# ADC.net
KiCad netlist of a schematic drawn in Altium Designer
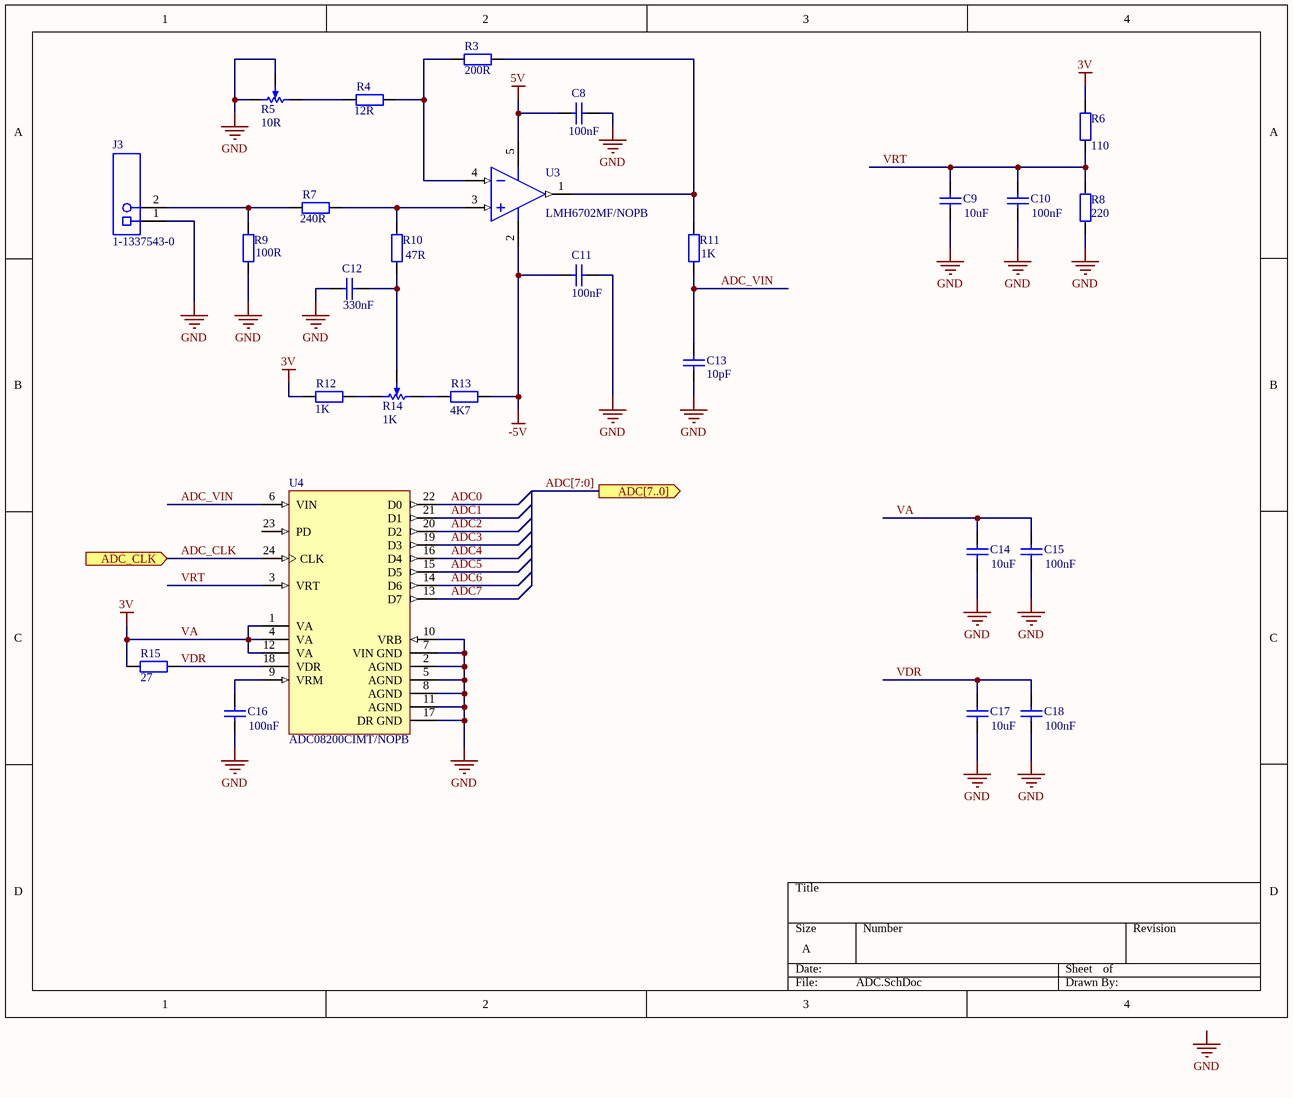
[diagram p0: ADC.SchDoc]

(export (version "E")
  (design (tool "Eeschema 10.0.6"))
  (components
    (comp (ref "C8")
      (value "100nF")
      (footprint "RAD-0.3")
      (description "Capacitor")
      (fields (field (name "Comment") "Cap") (field (name "PUBLISHER") "Altium Limited"))
      (libsource (lib "Miscellaneous Devices") (part "Cap"))
    )
    (comp (ref "C9")
      (value "10uF")
      (footprint "RAD-0.3")
      (description "Capacitor")
      (fields (field (name "Comment") "Cap") (field (name "PUBLISHER") "Altium Limited"))
      (libsource (lib "Miscellaneous Devices") (part "Cap"))
    )
    (comp (ref "C10")
      (value "100nF")
      (footprint "RAD-0.3")
      (description "Capacitor")
      (fields (field (name "Comment") "Cap") (field (name "PUBLISHER") "Altium Limited"))
      (libsource (lib "Miscellaneous Devices") (part "Cap"))
    )
    (comp (ref "C11")
      (value "100nF")
      (footprint "RAD-0.3")
      (description "Capacitor")
      (fields (field (name "Comment") "Cap") (field (name "PUBLISHER") "Altium Limited"))
      (libsource (lib "Miscellaneous Devices") (part "Cap"))
    )
    (comp (ref "C12")
      (value "330nF")
      (footprint "RAD-0.3")
      (description "Capacitor")
      (fields (field (name "Comment") "Cap") (field (name "PUBLISHER") "Altium Limited"))
      (libsource (lib "Miscellaneous Devices") (part "Cap"))
    )
    (comp (ref "C13")
      (value "10pF")
      (footprint "RAD-0.3")
      (description "Capacitor")
      (fields (field (name "Comment") "Cap") (field (name "PUBLISHER") "Altium Limited"))
      (libsource (lib "Miscellaneous Devices") (part "Cap"))
    )
    (comp (ref "C14")
      (value "10uF")
      (footprint "RAD-0.3")
      (description "Capacitor")
      (fields (field (name "Comment") "Cap") (field (name "PUBLISHER") "Altium Limited"))
      (libsource (lib "Miscellaneous Devices") (part "Cap"))
    )
    (comp (ref "C15")
      (value "100nF")
      (footprint "RAD-0.3")
      (description "Capacitor")
      (fields (field (name "Comment") "Cap") (field (name "PUBLISHER") "Altium Limited"))
      (libsource (lib "Miscellaneous Devices") (part "Cap"))
    )
    (comp (ref "C16")
      (value "100nF")
      (footprint "RAD-0.3")
      (description "Capacitor")
      (fields (field (name "Comment") "Cap") (field (name "PUBLISHER") "Altium Limited"))
      (libsource (lib "Miscellaneous Devices") (part "Cap"))
    )
    (comp (ref "C17")
      (value "10uF")
      (footprint "RAD-0.3")
      (description "Capacitor")
      (fields (field (name "Comment") "Cap") (field (name "PUBLISHER") "Altium Limited"))
      (libsource (lib "Miscellaneous Devices") (part "Cap"))
    )
    (comp (ref "C18")
      (value "100nF")
      (footprint "RAD-0.3")
      (description "Capacitor")
      (fields (field (name "Comment") "Cap") (field (name "PUBLISHER") "Altium Limited"))
      (libsource (lib "Miscellaneous Devices") (part "Cap"))
    )
    (comp (ref "J3")
      (value "1-1337543-0")
      (footprint "TECO-1-1337543-0_V")
      (fields (field (name "MANUFACTURER") "TE Connectivity"))
      (libsource (lib "Altium Content Vault") (part "CN-1P-F-R2_A"))
    )
    (comp (ref "R3")
      (value "200R")
      (footprint "AXIAL-0.4")
      (description "Resistor")
      (fields (field (name "Comment") "Res2") (field (name "PUBLISHER") "Altium Limited"))
      (libsource (lib "") (part "Res2_2"))
    )
    (comp (ref "R4")
      (value "12R")
      (footprint "AXIAL-0.4")
      (description "Resistor")
      (fields (field (name "Comment") "Res2") (field (name "PUBLISHER") "Altium Limited"))
      (libsource (lib "") (part "Res2_2"))
    )
    (comp (ref "R5")
      (value "10R")
      (footprint "POT4MM-2")
      (description "Square Trimming Potentiometer")
      (fields (field (name "PUBLISHER") "Altium Limited"))
      (libsource (lib "Miscellaneous Devices") (part "RPot SM"))
    )
    (comp (ref "R6")
      (value "110")
      (footprint "AXIAL-0.4")
      (description "Resistor")
      (fields (field (name "Comment") "Res2") (field (name "PUBLISHER") "Altium Limited"))
      (libsource (lib "Miscellaneous Devices") (part "Res2"))
    )
    (comp (ref "R7")
      (value "240R")
      (footprint "AXIAL-0.4")
      (description "Resistor")
      (fields (field (name "Comment") "Res2") (field (name "PUBLISHER") "Altium Limited"))
      (libsource (lib "") (part "Res2_2"))
    )
    (comp (ref "R8")
      (value "220")
      (footprint "AXIAL-0.4")
      (description "Resistor")
      (fields (field (name "Comment") "Res2") (field (name "PUBLISHER") "Altium Limited"))
      (libsource (lib "Miscellaneous Devices") (part "Res2"))
    )
    (comp (ref "R9")
      (value "100R")
      (footprint "AXIAL-0.4")
      (description "Resistor")
      (fields (field (name "Comment") "Res2") (field (name "PUBLISHER") "Altium Limited"))
      (libsource (lib "Miscellaneous Devices") (part "Res2"))
    )
    (comp (ref "R10")
      (value "47R")
      (footprint "AXIAL-0.4")
      (description "Resistor")
      (fields (field (name "Comment") "Res2") (field (name "PUBLISHER") "Altium Limited"))
      (libsource (lib "Miscellaneous Devices") (part "Res2"))
    )
    (comp (ref "R11")
      (value "1K")
      (footprint "AXIAL-0.4")
      (description "Resistor")
      (fields (field (name "Comment") "Res2") (field (name "PUBLISHER") "Altium Limited"))
      (libsource (lib "Miscellaneous Devices") (part "Res2"))
    )
    (comp (ref "R12")
      (value "1K")
      (footprint "AXIAL-0.4")
      (description "Resistor")
      (fields (field (name "Comment") "Res2") (field (name "PUBLISHER") "Altium Limited"))
      (libsource (lib "") (part "Res2_1"))
    )
    (comp (ref "R13")
      (value "4K7")
      (footprint "AXIAL-0.4")
      (description "Resistor")
      (fields (field (name "Comment") "Res2") (field (name "PUBLISHER") "Altium Limited"))
      (libsource (lib "") (part "Res2_1"))
    )
    (comp (ref "R14")
      (value "1K")
      (footprint "POT4MM-2")
      (description "Square Trimming Potentiometer")
      (fields (field (name "PUBLISHER") "Altium Limited"))
      (libsource (lib "Miscellaneous Devices") (part "RPot SM"))
    )
    (comp (ref "R15")
      (value "27")
      (footprint "AXIAL-0.4")
      (description "Resistor")
      (fields (field (name "Comment") "Res2") (field (name "PUBLISHER") "Altium Limited"))
      (libsource (lib "") (part "Res2_1"))
    )
    (comp (ref "U3")
      (value "LMH6702MF/NOPB")
      (footprint "DBV0005A_N")
      (description "1.7 GHz, Ultra Low Distortion, Wideband Op Amp, 5-pin SOT-23, Pb-Free")
      (fields (field (name "MANUFACTURER") "Texas Instruments"))
      (libsource (lib "Altium Content Vault") (part "AMP-OPA-LM7121-5"))
    )
    (comp (ref "U4")
      (value "ADC08200CIMT/NOPB")
      (footprint "PW0024A_M")
      (fields (field (name "MANUFACTURER") "Texas Instruments"))
      (libsource (lib "Altium Content Vault") (part "CON-ADC-ADC08L060CIMT"))
    )
  )
  (nets
    (net (code "2") (name "-5V") (class "Default")
      (node (ref "C11") (pin "1") (pinfunction "1_1") (pintype "passive"))
      (node (ref "R13") (pin "1") (pinfunction "1_1") (pintype "passive"))
      (node (ref "U3") (pin "2") (pinfunction "V-_2") (pintype "power_in"))
    )
    (net (code "3") (name "/ADC0") (class "Default")
      (node (ref "U4") (pin "22") (pinfunction "D0_22") (pintype "output"))
    )
    (net (code "4") (name "/ADC1") (class "Default")
      (node (ref "U4") (pin "21") (pinfunction "D1_21") (pintype "output"))
    )
    (net (code "5") (name "/ADC2") (class "Default")
      (node (ref "U4") (pin "20") (pinfunction "D2_20") (pintype "output"))
    )
    (net (code "6") (name "/ADC3") (class "Default")
      (node (ref "U4") (pin "19") (pinfunction "D3_19") (pintype "output"))
    )
    (net (code "7") (name "/ADC4") (class "Default")
      (node (ref "U4") (pin "16") (pinfunction "D4_16") (pintype "output"))
    )
    (net (code "8") (name "/ADC5") (class "Default")
      (node (ref "U4") (pin "15") (pinfunction "D5_15") (pintype "output"))
    )
    (net (code "9") (name "/ADC6") (class "Default")
      (node (ref "U4") (pin "14") (pinfunction "D6_14") (pintype "output"))
    )
    (net (code "10") (name "/ADC7") (class "Default")
      (node (ref "U4") (pin "13") (pinfunction "D7_13") (pintype "output"))
    )
    (net (code "11") (name "/ADC_CLK") (class "Default")
      (node (ref "U4") (pin "24") (pinfunction "CLK_24") (pintype "input"))
    )
    (net (code "12") (name "/ADC_VIN") (class "Default")
      (node (ref "C13") (pin "2") (pinfunction "2_2") (pintype "passive"))
      (node (ref "R11") (pin "1") (pinfunction "1_1") (pintype "passive"))
      (node (ref "U4") (pin "6") (pinfunction "VIN_6") (pintype "input"))
    )
    (net (code "13") (name "/VDR") (class "Default")
      (node (ref "C17") (pin "2") (pinfunction "2_2") (pintype "passive"))
      (node (ref "C18") (pin "2") (pinfunction "2_2") (pintype "passive"))
      (node (ref "R15") (pin "1") (pinfunction "1_1") (pintype "passive"))
      (node (ref "U4") (pin "18") (pinfunction "VDR_18") (pintype "power_in"))
    )
    (net (code "14") (name "/VRT") (class "Default")
      (node (ref "C10") (pin "2") (pinfunction "2_2") (pintype "passive"))
      (node (ref "C9") (pin "2") (pinfunction "2_2") (pintype "passive"))
      (node (ref "R6") (pin "1") (pinfunction "1_1") (pintype "passive"))
      (node (ref "R8") (pin "2") (pinfunction "2_2") (pintype "passive"))
      (node (ref "U4") (pin "3") (pinfunction "VRT_3") (pintype "input"))
    )
    (net (code "16") (name "3V") (class "Default")
      (node (ref "C14") (pin "2") (pinfunction "2_2") (pintype "passive"))
      (node (ref "C15") (pin "2") (pinfunction "2_2") (pintype "passive"))
      (node (ref "R12") (pin "2") (pinfunction "2_2") (pintype "passive"))
      (node (ref "R15") (pin "2") (pinfunction "2_2") (pintype "passive"))
      (node (ref "R6") (pin "2") (pinfunction "2_2") (pintype "passive"))
      (node (ref "U4") (pin "1") (pinfunction "VA_1") (pintype "power_in"))
      (node (ref "U4") (pin "12") (pinfunction "VA_12") (pintype "power_in"))
      (node (ref "U4") (pin "4") (pinfunction "VA_4") (pintype "power_in"))
    )
    (net (code "17") (name "5V") (class "Default")
      (node (ref "C8") (pin "1") (pinfunction "1_1") (pintype "passive"))
      (node (ref "U3") (pin "5") (pinfunction "V+_5") (pintype "power_in"))
    )
    (net (code "18") (name "GND") (class "Default")
      (node (ref "C10") (pin "1") (pinfunction "1_1") (pintype "passive"))
      (node (ref "C11") (pin "2") (pinfunction "2_2") (pintype "passive"))
      (node (ref "C12") (pin "1") (pinfunction "1_1") (pintype "passive"))
      (node (ref "C13") (pin "1") (pinfunction "1_1") (pintype "passive"))
      (node (ref "C14") (pin "1") (pinfunction "1_1") (pintype "passive"))
      (node (ref "C15") (pin "1") (pinfunction "1_1") (pintype "passive"))
      (node (ref "C16") (pin "1") (pinfunction "1_1") (pintype "passive"))
      (node (ref "C17") (pin "1") (pinfunction "1_1") (pintype "passive"))
      (node (ref "C18") (pin "1") (pinfunction "1_1") (pintype "passive"))
      (node (ref "C8") (pin "2") (pinfunction "2_2") (pintype "passive"))
      (node (ref "C9") (pin "1") (pinfunction "1_1") (pintype "passive"))
      (node (ref "J3") (pin "1") (pinfunction "1_1") (pintype "passive"))
      (node (ref "R5") (pin "CW") (pinfunction "+_CW") (pintype "passive"))
      (node (ref "R5") (pin "W") (pinfunction "W_W") (pintype "passive"))
      (node (ref "R8") (pin "1") (pinfunction "1_1") (pintype "passive"))
      (node (ref "R9") (pin "1") (pinfunction "1_1") (pintype "passive"))
      (node (ref "U4") (pin "10") (pinfunction "VRB_10") (pintype "input"))
      (node (ref "U4") (pin "11") (pinfunction "AGND_11") (pintype "power_in"))
      (node (ref "U4") (pin "17") (pinfunction "DR_GND_17") (pintype "power_in"))
      (node (ref "U4") (pin "2") (pinfunction "AGND_2") (pintype "power_in"))
      (node (ref "U4") (pin "5") (pinfunction "AGND_5") (pintype "power_in"))
      (node (ref "U4") (pin "7") (pinfunction "VIN_GND_7") (pintype "power_in"))
      (node (ref "U4") (pin "8") (pinfunction "AGND_8") (pintype "power_in"))
    )
    (net (code "19") (name "Net-(C12-Pad2)") (class "Default")
      (node (ref "C12") (pin "2") (pinfunction "2_2") (pintype "passive"))
      (node (ref "R10") (pin "1") (pinfunction "1_1") (pintype "passive"))
      (node (ref "R14") (pin "W") (pinfunction "W_W") (pintype "passive"))
    )
    (net (code "20") (name "Net-(J3-Pad2)") (class "Default")
      (node (ref "J3") (pin "2") (pinfunction "2_2") (pintype "passive"))
      (node (ref "R7") (pin "1") (pinfunction "1_1") (pintype "passive"))
      (node (ref "R9") (pin "2") (pinfunction "2_2") (pintype "passive"))
    )
    (net (code "21") (name "Net-(R5--)") (class "Default")
      (node (ref "R4") (pin "1") (pinfunction "1_1") (pintype "passive"))
      (node (ref "R5") (pin "CCW") (pinfunction "-_CCW") (pintype "passive"))
    )
    (net (code "22") (name "Net-(R14-+)") (class "Default")
      (node (ref "R12") (pin "1") (pinfunction "1_1") (pintype "passive"))
      (node (ref "R14") (pin "CW") (pinfunction "+_CW") (pintype "passive"))
    )
    (net (code "23") (name "Net-(R14--)") (class "Default")
      (node (ref "R13") (pin "2") (pinfunction "2_2") (pintype "passive"))
      (node (ref "R14") (pin "CCW") (pinfunction "-_CCW") (pintype "passive"))
    )
    (net (code "24") (name "Net-(U3-IN+)") (class "Default")
      (node (ref "R10") (pin "2") (pinfunction "2_2") (pintype "passive"))
      (node (ref "R7") (pin "2") (pinfunction "2_2") (pintype "passive"))
      (node (ref "U3") (pin "3") (pinfunction "IN+_3") (pintype "input"))
    )
    (net (code "25") (name "Net-(U3-IN-)") (class "Default")
      (node (ref "R3") (pin "1") (pinfunction "1_1") (pintype "passive"))
      (node (ref "R4") (pin "2") (pinfunction "2_2") (pintype "passive"))
      (node (ref "U3") (pin "4") (pinfunction "IN-_4") (pintype "input"))
    )
    (net (code "26") (name "Net-(U3-OUT)") (class "Default")
      (node (ref "R11") (pin "2") (pinfunction "2_2") (pintype "passive"))
      (node (ref "R3") (pin "2") (pinfunction "2_2") (pintype "passive"))
      (node (ref "U3") (pin "1") (pinfunction "OUT_1") (pintype "output"))
    )
    (net (code "27") (name "Net-(U4-VRM)") (class "Default")
      (node (ref "C16") (pin "2") (pinfunction "2_2") (pintype "passive"))
      (node (ref "U4") (pin "9") (pinfunction "VRM_9") (pintype "input"))
    )
    (net (code "28") (name "unconnected-(U4-PD-Pad23)") (class "Default")
      (node (ref "U4") (pin "23") (pinfunction "PD_23") (pintype "input"))
    )
  )
)
